# HedleySensorRevD1.net
KiCad netlist of a schematic drawn in EAGLE
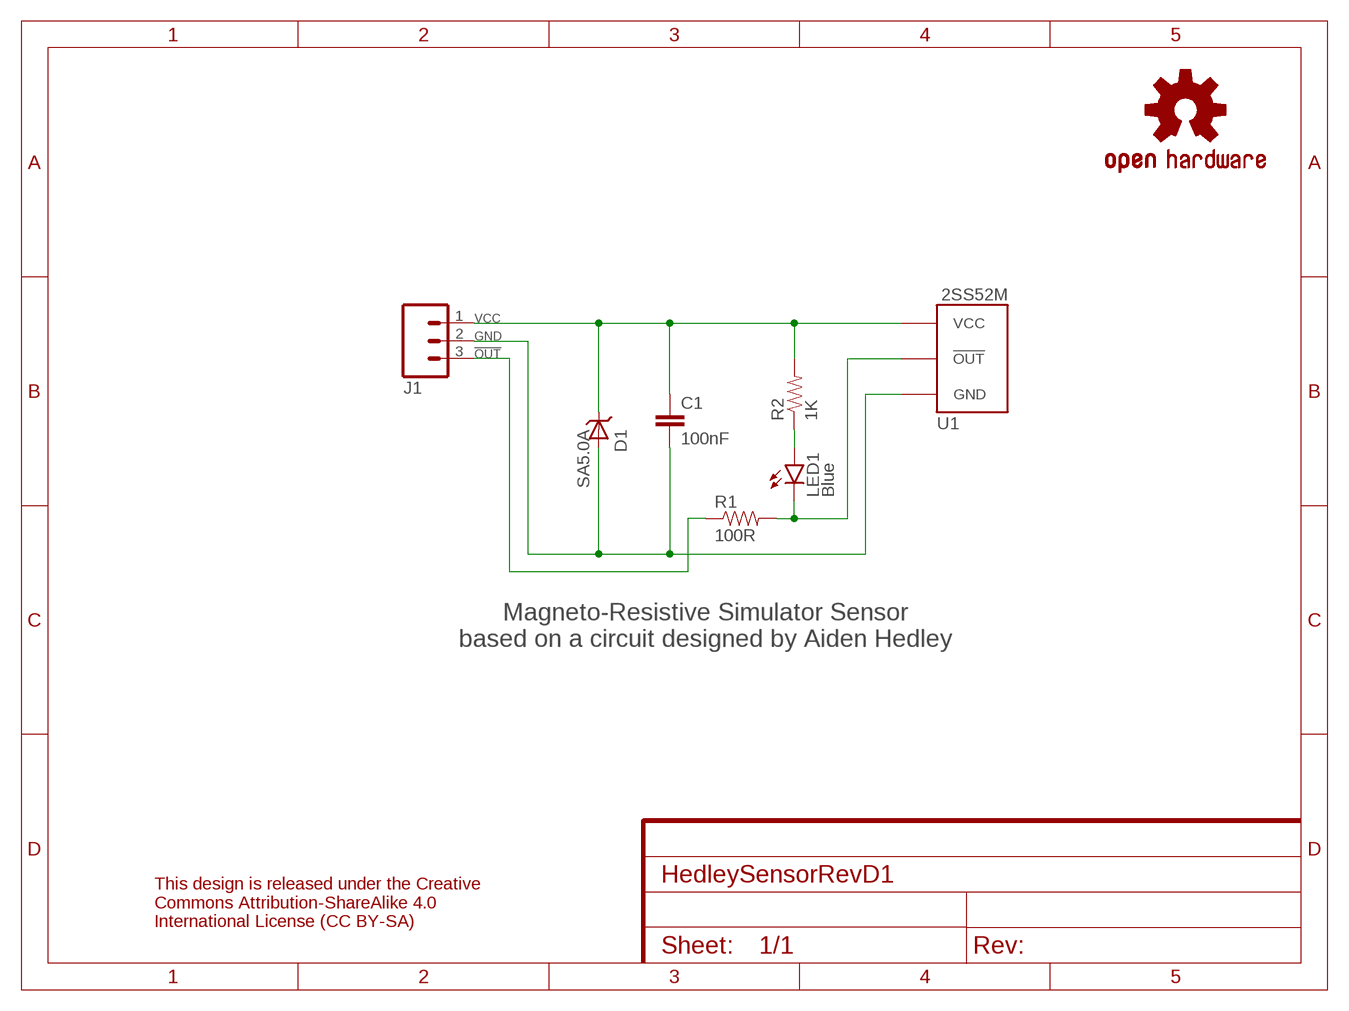
[diagram p0: schematic, sheet 1]

(export (version "E")
  (design (tool "Eeschema 10.0.6"))
  (components
    (comp (ref "C1")
      (value "100nF")
      (footprint "eagle-import:CAP-PTH-SMALL")
      (libsource (lib "eagle-import") (part "CAPPTH"))
    )
    (comp (ref "D1")
      (value "SA5.0A")
      (footprint "eagle-import:DO41_TVS_UNI")
      (libsource (lib "eagle-import") (part "SA5.0A"))
    )
    (comp (ref "J1")
      (value "M03PTH")
      (footprint "eagle-import:1X03")
      (libsource (lib "eagle-import") (part "M03PTH"))
    )
    (comp (ref "LED1")
      (value "Blue")
      (footprint "eagle-import:LED3MM")
      (libsource (lib "eagle-import") (part "LED3MM"))
    )
    (comp (ref "LOGO1")
      (value "OSHW-LOGOS")
      (footprint "eagle-import:OSHW-LOGO-S")
      (libsource (lib "eagle-import") (part "OSHW-LOGOS"))
    )
    (comp (ref "R1")
      (value "100R")
      (footprint "eagle-import:AXIAL-0.4")
      (libsource (lib "eagle-import") (part "RESISTORPTH-1/4W"))
    )
    (comp (ref "R2")
      (value "1K")
      (footprint "eagle-import:AXIAL-0.4")
      (libsource (lib "eagle-import") (part "RESISTORPTH-1/4W"))
    )
    (comp (ref "U1")
      (value "2SS52MFLAT")
      (footprint "eagle-import:2SS52M_FLAT")
      (libsource (lib "eagle-import") (part "2SS52MFLAT"))
    )
  )
  (nets
    (net (code "1") (name "/GND") (class "Default")
      (node (ref "C1") (pin "2") (pinfunction "2_2") (pintype "passive"))
      (node (ref "D1") (pin "ANODE") (pinfunction "ANODE_ANODE") (pintype "passive"))
      (node (ref "J1") (pin "2") (pinfunction "2_2") (pintype "passive"))
      (node (ref "U1") (pin "P$1") (pinfunction "GND_P$1") (pintype "bidirectional"))
    )
    (net (code "2") (name "/VCC") (class "Default")
      (node (ref "C1") (pin "1") (pinfunction "1_1") (pintype "passive"))
      (node (ref "D1") (pin "CATHODE") (pinfunction "CATHODE_CATHODE") (pintype "passive"))
      (node (ref "J1") (pin "1") (pinfunction "1_1") (pintype "passive"))
      (node (ref "R2") (pin "P$2") (pinfunction "2_P$2") (pintype "passive"))
      (node (ref "U1") (pin "P$3") (pinfunction "VCC_P$3") (pintype "bidirectional"))
    )
    (net (code "3") (name "/~{OUT}") (class "Default")
      (node (ref "J1") (pin "3") (pinfunction "3_3") (pintype "passive"))
      (node (ref "R1") (pin "P$1") (pinfunction "1_P$1") (pintype "passive"))
    )
    (net (code "4") (name "Net-(LED1-C)") (class "Default")
      (node (ref "LED1") (pin "K") (pinfunction "C_K") (pintype "passive"))
      (node (ref "R1") (pin "P$2") (pinfunction "2_P$2") (pintype "passive"))
      (node (ref "U1") (pin "P$2") (pinfunction "~{OUT}_P$2") (pintype "bidirectional"))
    )
    (net (code "5") (name "Net-(R2-1)") (class "Default")
      (node (ref "LED1") (pin "A") (pinfunction "A_A") (pintype "passive"))
      (node (ref "R2") (pin "P$1") (pinfunction "1_P$1") (pintype "passive"))
    )
  )
)
